# Precharge_schematic.net
KiCad netlist of a schematic drawn in Altium Designer
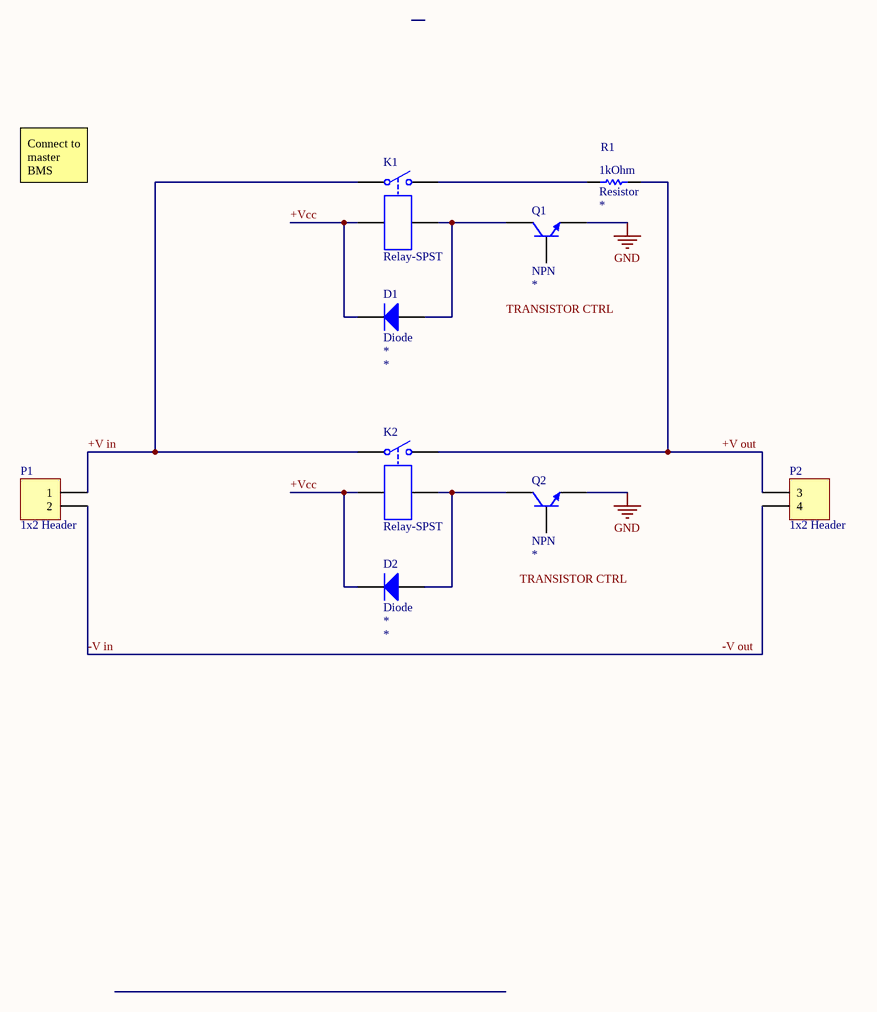
[diagram p0: Precharge_schematic.SchDoc]

(export (version "E")
  (design (tool "Eeschema 10.0.6"))
  (components
    (comp (ref "1kOhm")
      (value "Resistor")
      (footprint "0603 - Resistor")
      (fields (field (name "ALTIUM_VALUE") "*"))
      (libsource (lib "General") (part "Resistor"))
    )
    (comp (ref "D1")
      (value "Diode")
      (fields (field (name "ALTIUM_VALUE") "*") (field (name "MANUFACTURER PART NUMBER") "*"))
      (libsource (lib "General") (part "Diode"))
    )
    (comp (ref "D2")
      (value "Diode")
      (fields (field (name "ALTIUM_VALUE") "*") (field (name "MANUFACTURER PART NUMBER") "*"))
      (libsource (lib "General") (part "Diode"))
    )
    (comp (ref "K1")
      (value "Relay-SPST")
      (footprint "MODULE4")
      (description "Single-Pole Single-Throw Relay")
      (fields (field (name "PUBLISHER") "Altium Limited"))
      (libsource (lib "Miscellaneous Devices") (part "Relay-SPST"))
    )
    (comp (ref "K2")
      (value "Relay-SPST")
      (footprint "MODULE4")
      (description "Single-Pole Single-Throw Relay")
      (fields (field (name "PUBLISHER") "Altium Limited"))
      (libsource (lib "Miscellaneous Devices") (part "Relay-SPST"))
    )
    (comp (ref "P1")
      (value "1x2 Header")
      (description "1x2 Pin Header")
      (libsource (lib "GeneralConnectors") (part "1x2 Header"))
    )
    (comp (ref "P2")
      (value "1x2 Header")
      (description "1x2 Pin Header")
      (libsource (lib "") (part "1x2 Header_1"))
    )
    (comp (ref "Q1")
      (value "NPN")
      (description "NPN Bipolar Transistor")
      (fields (field (name "ALTIUM_VALUE") "*"))
      (libsource (lib "General") (part "NPN"))
    )
    (comp (ref "Q2")
      (value "NPN")
      (description "NPN Bipolar Transistor")
      (fields (field (name "ALTIUM_VALUE") "*"))
      (libsource (lib "General") (part "NPN"))
    )
  )
  (nets
    (net (code "1") (name "/+V in") (class "Default")
      (node (ref "K1") (pin "1") (pinfunction "1_1") (pintype "passive"))
      (node (ref "K2") (pin "1") (pinfunction "1_1") (pintype "passive"))
      (node (ref "P1") (pin "1") (pinfunction "1_1") (pintype "passive"))
    )
    (net (code "2") (name "/+V out") (class "Default")
      (node (ref "1kOhm") (pin "2") (pinfunction "2_2") (pintype "passive"))
      (node (ref "K2") (pin "2") (pinfunction "2_2") (pintype "passive"))
      (node (ref "P2") (pin "3") (pinfunction "3_3") (pintype "passive"))
    )
    (net (code "3") (name "/+Vcc") (class "Default")
      (node (ref "D1") (pin "2") (pinfunction "K_2") (pintype "passive"))
      (node (ref "D2") (pin "2") (pinfunction "K_2") (pintype "passive"))
      (node (ref "K1") (pin "3") (pinfunction "3_3") (pintype "passive"))
      (node (ref "K2") (pin "3") (pinfunction "3_3") (pintype "passive"))
    )
    (net (code "4") (name "/-V in") (class "Default")
      (node (ref "P1") (pin "2") (pinfunction "2_2") (pintype "passive"))
      (node (ref "P2") (pin "4") (pinfunction "4_4") (pintype "passive"))
    )
    (net (code "6") (name "GND") (class "Default")
      (node (ref "Q1") (pin "3") (pinfunction "E_3") (pintype "passive"))
      (node (ref "Q2") (pin "3") (pinfunction "E_3") (pintype "passive"))
    )
    (net (code "7") (name "Net-(1kOhm-Pad1)") (class "Default")
      (node (ref "1kOhm") (pin "1") (pinfunction "1_1") (pintype "passive"))
      (node (ref "K1") (pin "2") (pinfunction "2_2") (pintype "passive"))
    )
    (net (code "8") (name "Net-(D1-A)") (class "Default")
      (node (ref "D1") (pin "1") (pinfunction "A_1") (pintype "passive"))
      (node (ref "K1") (pin "4") (pinfunction "4_4") (pintype "passive"))
      (node (ref "Q1") (pin "1") (pinfunction "C_1") (pintype "passive"))
    )
    (net (code "9") (name "Net-(D2-A)") (class "Default")
      (node (ref "D2") (pin "1") (pinfunction "A_1") (pintype "passive"))
      (node (ref "K2") (pin "4") (pinfunction "4_4") (pintype "passive"))
      (node (ref "Q2") (pin "1") (pinfunction "C_1") (pintype "passive"))
    )
    (net (code "10") (name "unconnected-(Q1-B-Pad2)") (class "Default")
      (node (ref "Q1") (pin "2") (pinfunction "B_2") (pintype "passive"))
    )
    (net (code "11") (name "unconnected-(Q2-B-Pad2)") (class "Default")
      (node (ref "Q2") (pin "2") (pinfunction "B_2") (pintype "passive"))
    )
  )
)
